# pcb_paneles.net
KiCad netlist of a schematic drawn in EAGLE
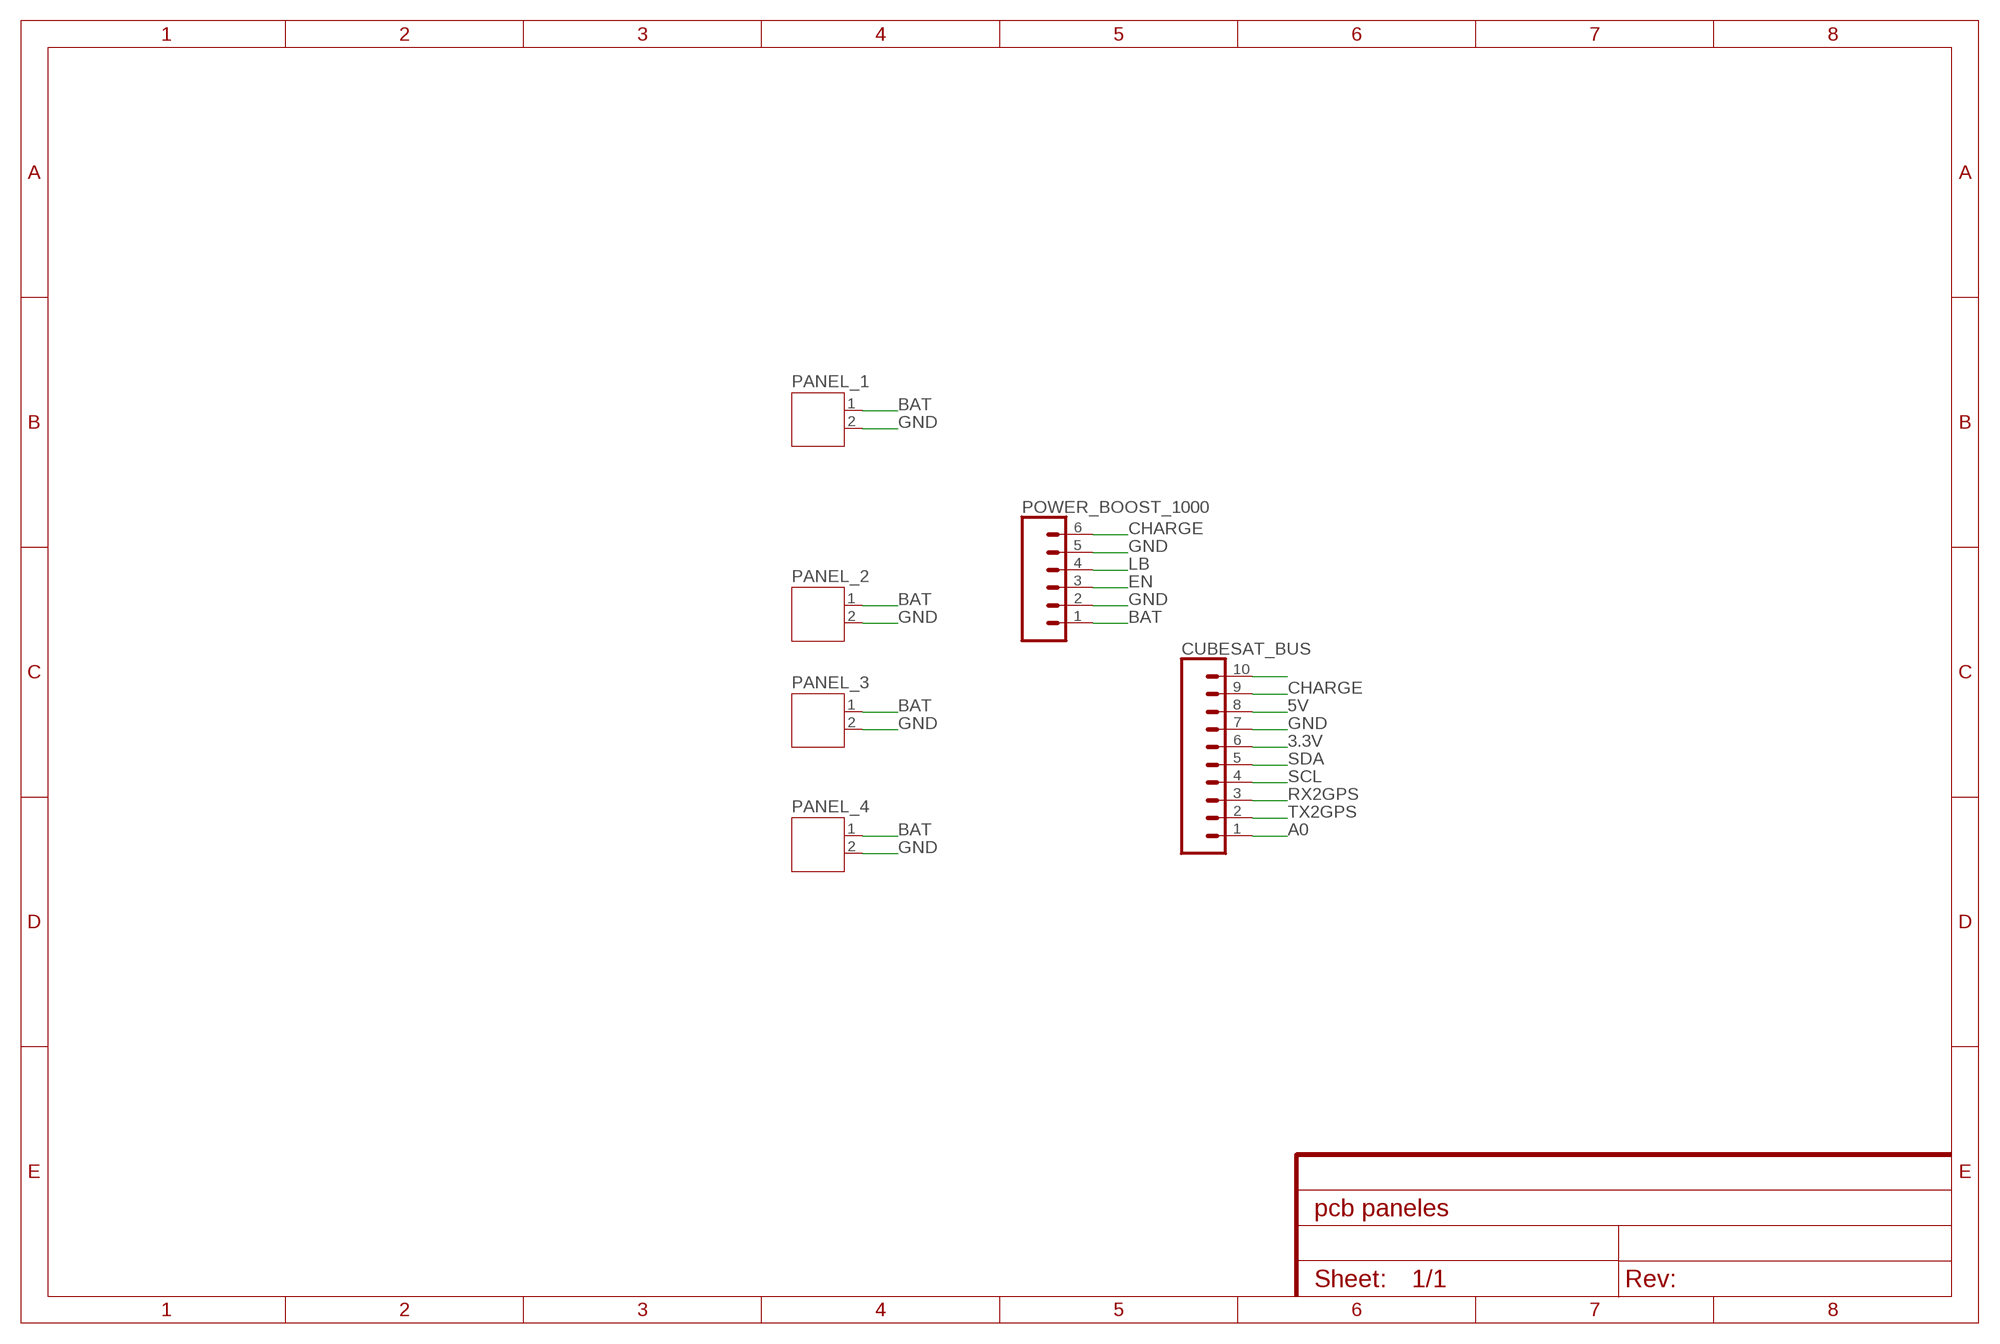
[diagram p0: schematic, sheet 1]

(export (version "E")
  (design (tool "Eeschema 10.0.6"))
  (components
    (comp (ref "CUBESAT_BUS")
      (value "CONN_10\"")
      (footprint "eagle-import:1X10")
      (libsource (lib "eagle-import") (part "CONN_10{dblquote}"))
    )
    (comp (ref "PANEL_1")
      (value "JST-PH2")
      (footprint "eagle-import:JST-PH2")
      (libsource (lib "eagle-import") (part "JST-PH2"))
    )
    (comp (ref "PANEL_2")
      (value "JST-PH2")
      (footprint "eagle-import:JST-PH2")
      (libsource (lib "eagle-import") (part "JST-PH2"))
    )
    (comp (ref "PANEL_3")
      (value "JST-PH2")
      (footprint "eagle-import:JST-PH2")
      (libsource (lib "eagle-import") (part "JST-PH2"))
    )
    (comp (ref "PANEL_4")
      (value "JST-PH2")
      (footprint "eagle-import:JST-PH2")
      (libsource (lib "eagle-import") (part "JST-PH2"))
    )
    (comp (ref "POWER_BOOST_1000")
      (value "CONN_06SILK_FEMALE_PTH")
      (footprint "eagle-import:1X06")
      (libsource (lib "eagle-import") (part "CONN_06SILK_FEMALE_PTH"))
    )
  )
  (nets
    (net (code "1") (name "/3.3V") (class "Default")
      (node (ref "CUBESAT_BUS") (pin "6") (pinfunction "6_6") (pintype "passive"))
    )
    (net (code "2") (name "/5V") (class "Default")
      (node (ref "CUBESAT_BUS") (pin "8") (pinfunction "8_8") (pintype "passive"))
    )
    (net (code "3") (name "/A0") (class "Default")
      (node (ref "CUBESAT_BUS") (pin "1") (pinfunction "1_1") (pintype "passive"))
    )
    (net (code "4") (name "/BAT") (class "Default")
      (node (ref "PANEL_1") (pin "1") (pinfunction "1_1") (pintype "passive"))
      (node (ref "PANEL_2") (pin "1") (pinfunction "1_1") (pintype "passive"))
      (node (ref "PANEL_3") (pin "1") (pinfunction "1_1") (pintype "passive"))
      (node (ref "PANEL_4") (pin "1") (pinfunction "1_1") (pintype "passive"))
      (node (ref "POWER_BOOST_1000") (pin "1") (pinfunction "1_1") (pintype "passive"))
    )
    (net (code "5") (name "/CHARGE") (class "Default")
      (node (ref "CUBESAT_BUS") (pin "9") (pinfunction "9_9") (pintype "passive"))
      (node (ref "POWER_BOOST_1000") (pin "6") (pinfunction "6_6") (pintype "passive"))
    )
    (net (code "6") (name "/EN") (class "Default")
      (node (ref "POWER_BOOST_1000") (pin "3") (pinfunction "3_3") (pintype "passive"))
    )
    (net (code "7") (name "/GND") (class "Default")
      (node (ref "CUBESAT_BUS") (pin "7") (pinfunction "7_7") (pintype "passive"))
      (node (ref "PANEL_1") (pin "2") (pinfunction "2_2") (pintype "passive"))
      (node (ref "PANEL_2") (pin "2") (pinfunction "2_2") (pintype "passive"))
      (node (ref "PANEL_3") (pin "2") (pinfunction "2_2") (pintype "passive"))
      (node (ref "PANEL_4") (pin "2") (pinfunction "2_2") (pintype "passive"))
      (node (ref "POWER_BOOST_1000") (pin "2") (pinfunction "2_2") (pintype "passive"))
      (node (ref "POWER_BOOST_1000") (pin "5") (pinfunction "5_5") (pintype "passive"))
    )
    (net (code "8") (name "/LB") (class "Default")
      (node (ref "POWER_BOOST_1000") (pin "4") (pinfunction "4_4") (pintype "passive"))
    )
    (net (code "9") (name "/RX2GPS") (class "Default")
      (node (ref "CUBESAT_BUS") (pin "3") (pinfunction "3_3") (pintype "passive"))
    )
    (net (code "10") (name "/SCL") (class "Default")
      (node (ref "CUBESAT_BUS") (pin "4") (pinfunction "4_4") (pintype "passive"))
    )
    (net (code "11") (name "/SDA") (class "Default")
      (node (ref "CUBESAT_BUS") (pin "5") (pinfunction "5_5") (pintype "passive"))
    )
    (net (code "12") (name "/TX2GPS") (class "Default")
      (node (ref "CUBESAT_BUS") (pin "2") (pinfunction "2_2") (pintype "passive"))
    )
    (net (code "13") (name "unconnected-(CUBESAT_BUS-Pad10)") (class "Default")
      (node (ref "CUBESAT_BUS") (pin "10") (pinfunction "10_10") (pintype "passive"))
    )
  )
)
